# working.net
KiCad netlist of a schematic drawn in EAGLE
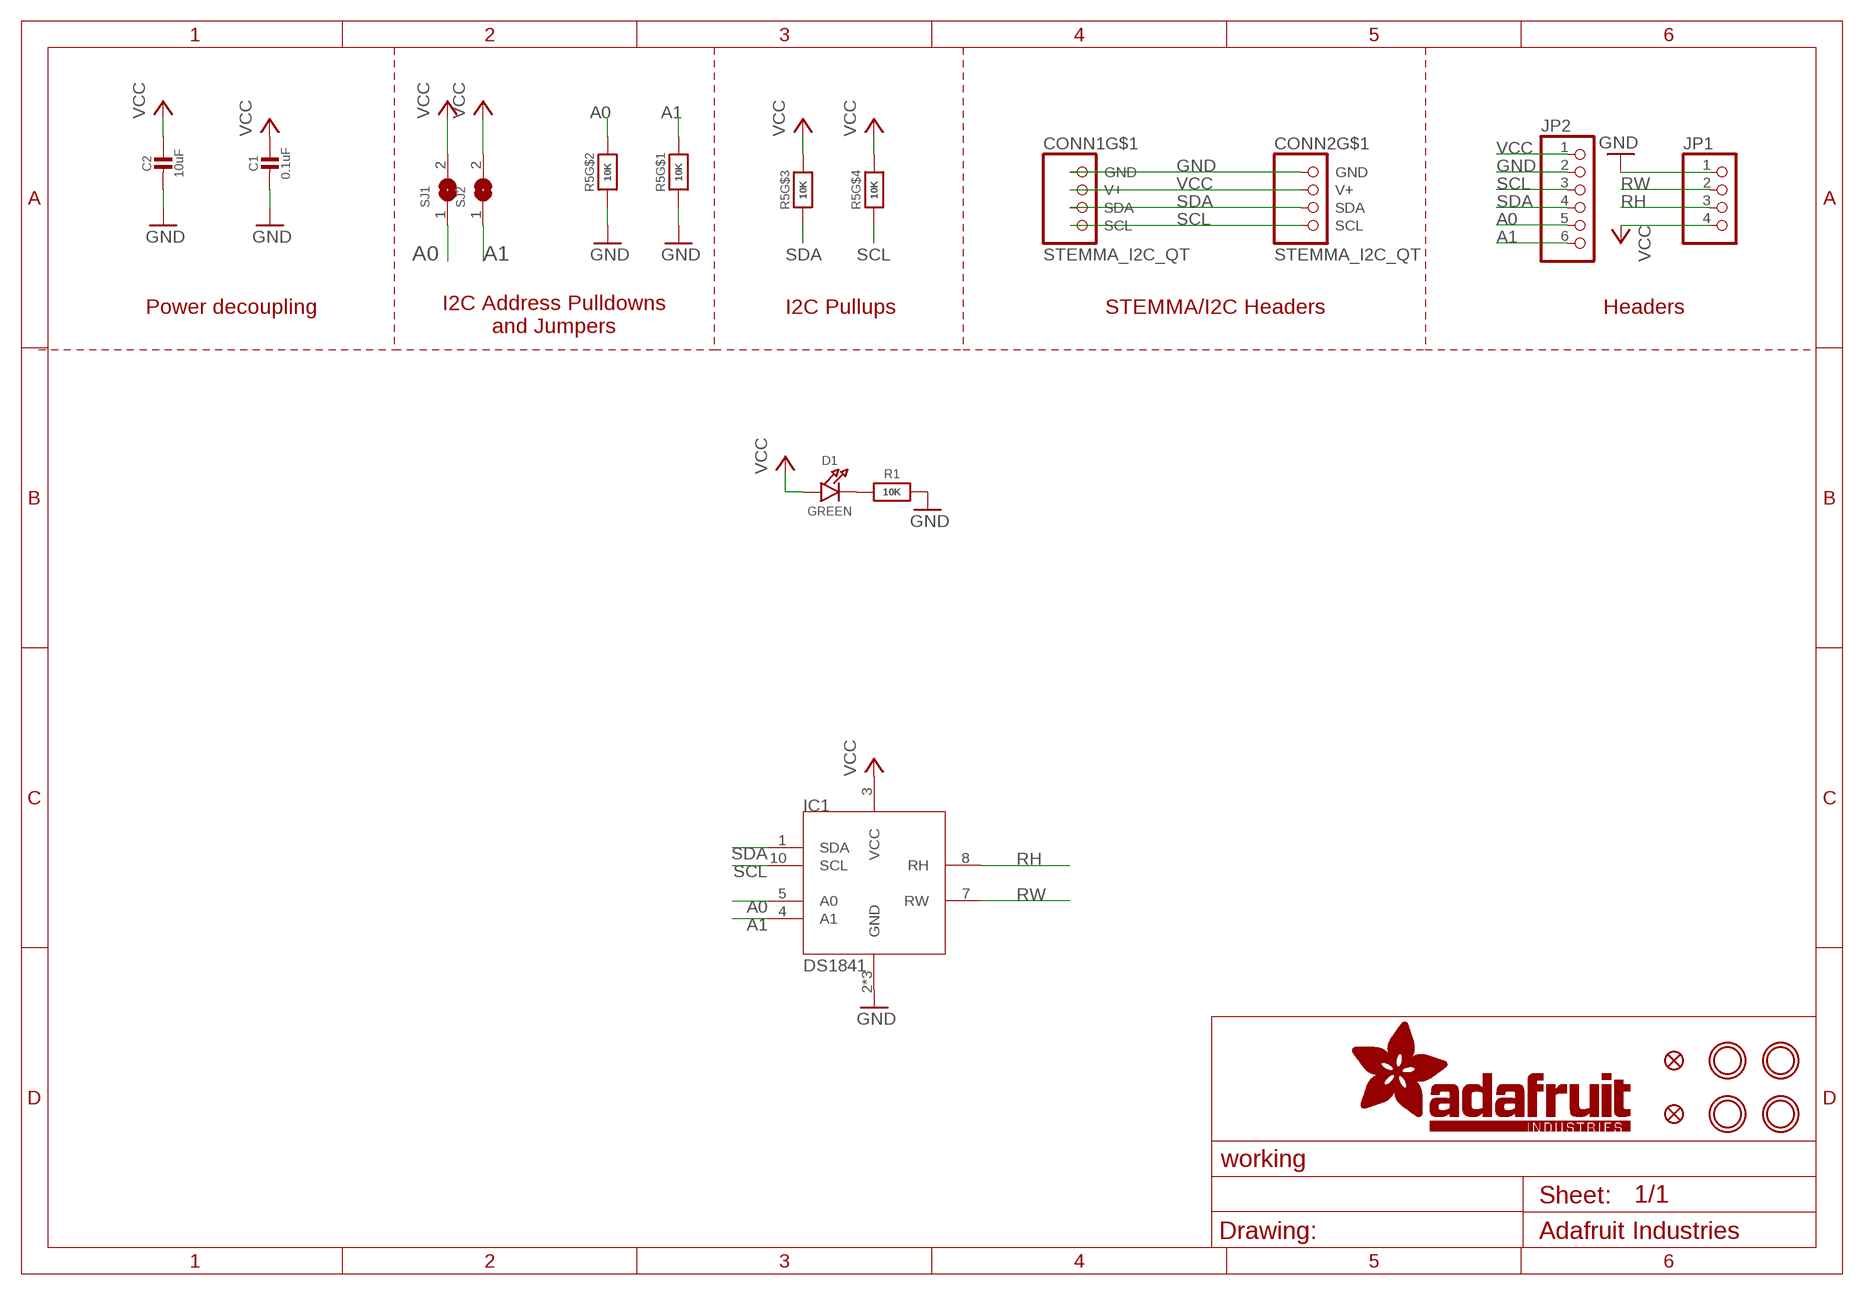
[diagram p0: schematic, sheet 1]

(export (version "E")
  (design (tool "Eeschema 10.0.6"))
  (components
    (comp (ref "C1")
      (value "0.1uF")
      (footprint "eagle-import:0603-NO")
      (libsource (lib "eagle-import") (part "CAP_CERAMIC0603_NO"))
    )
    (comp (ref "C2")
      (value "10uF")
      (footprint "eagle-import:0805-NO")
      (libsource (lib "eagle-import") (part "CAP_CERAMIC0805-NOOUTLINE"))
    )
    (comp (ref "CONN1")
      (value "STEMMA_I2C_QT")
      (footprint "eagle-import:JST_SH4")
      (libsource (lib "eagle-import") (part "STEMMA_I2C_QT"))
    )
    (comp (ref "CONN2")
      (value "STEMMA_I2C_QT")
      (footprint "eagle-import:JST_SH4")
      (libsource (lib "eagle-import") (part "STEMMA_I2C_QT"))
    )
    (comp (ref "D1")
      (value "GREEN")
      (footprint "eagle-import:CHIPLED_0603_NOOUTLINE")
      (libsource (lib "eagle-import") (part "LED0603_NOOUTLINE"))
    )
    (comp (ref "FID1")
      (value "FIDUCIAL_1MM")
      (footprint "eagle-import:FIDUCIAL_1MM")
      (libsource (lib "eagle-import") (part "FIDUCIAL_1MM"))
    )
    (comp (ref "FID2")
      (value "FIDUCIAL_1MM")
      (footprint "eagle-import:FIDUCIAL_1MM")
      (libsource (lib "eagle-import") (part "FIDUCIAL_1MM"))
    )
    (comp (ref "IC1")
      (value "DS1841")
      (footprint "eagle-import:DFN10_3X3MM")
      (libsource (lib "eagle-import") (part "DS1841"))
    )
    (comp (ref "JP1")
      (value "HEADER-1X4ROUND")
      (footprint "eagle-import:1X04_ROUND")
      (libsource (lib "eagle-import") (part "HEADER-1X4ROUND"))
    )
    (comp (ref "JP2")
      (value "HEADER-1X6ROUND")
      (footprint "eagle-import:1X06_ROUND")
      (libsource (lib "eagle-import") (part "HEADER-1X6ROUND"))
    )
    (comp (ref "R1")
      (value "10K")
      (footprint "eagle-import:0603-NO")
      (libsource (lib "eagle-import") (part "RESISTOR_0603_NOOUT"))
    )
    (comp (ref "R5")
      (value "10K")
      (footprint "eagle-import:RESPACK_4X0603")
      (libsource (lib "eagle-import") (part "RESISTOR_4PACK"))
    )
    (comp (ref "SJ1")
      (value "SOLDERJUMPER")
      (footprint "eagle-import:SOLDERJUMPER_ARROW_NOPASTE")
      (libsource (lib "eagle-import") (part "SOLDERJUMPER"))
    )
    (comp (ref "SJ2")
      (value "SOLDERJUMPER")
      (footprint "eagle-import:SOLDERJUMPER_ARROW_NOPASTE")
      (libsource (lib "eagle-import") (part "SOLDERJUMPER"))
    )
    (comp (ref "U$2")
      (value "MOUNTINGHOLE2.5")
      (footprint "eagle-import:MOUNTINGHOLE_2.5_PLATED")
      (libsource (lib "eagle-import") (part "MOUNTINGHOLE2.5"))
    )
    (comp (ref "U$3")
      (value "MOUNTINGHOLE2.5")
      (footprint "eagle-import:MOUNTINGHOLE_2.5_PLATED")
      (libsource (lib "eagle-import") (part "MOUNTINGHOLE2.5"))
    )
    (comp (ref "U$6")
      (value "MOUNTINGHOLE2.5")
      (footprint "eagle-import:MOUNTINGHOLE_2.5_PLATED")
      (libsource (lib "eagle-import") (part "MOUNTINGHOLE2.5"))
    )
    (comp (ref "U$7")
      (value "MOUNTINGHOLE2.5")
      (footprint "eagle-import:MOUNTINGHOLE_2.5_PLATED")
      (libsource (lib "eagle-import") (part "MOUNTINGHOLE2.5"))
    )
  )
  (nets
    (net (code "1") (name "/A0") (class "Default")
      (node (ref "IC1") (pin "5") (pinfunction "A0_5") (pintype "input"))
      (node (ref "JP2") (pin "5") (pinfunction "5_5") (pintype "passive"))
      (node (ref "R5") (pin "7") (pinfunction "2_7") (pintype "passive"))
      (node (ref "SJ1") (pin "1") (pinfunction "1_1") (pintype "passive"))
    )
    (net (code "2") (name "/A1") (class "Default")
      (node (ref "IC1") (pin "4") (pinfunction "A1_4") (pintype "input"))
      (node (ref "JP2") (pin "6") (pinfunction "6_6") (pintype "passive"))
      (node (ref "R5") (pin "8") (pinfunction "2_8") (pintype "passive"))
      (node (ref "SJ2") (pin "1") (pinfunction "1_1") (pintype "passive"))
    )
    (net (code "3") (name "/RH") (class "Default")
      (node (ref "IC1") (pin "8") (pinfunction "RH_8") (pintype "passive"))
      (node (ref "JP1") (pin "3") (pinfunction "3_3") (pintype "passive"))
    )
    (net (code "4") (name "/RW") (class "Default")
      (node (ref "IC1") (pin "7") (pinfunction "RW_7") (pintype "passive"))
      (node (ref "JP1") (pin "2") (pinfunction "2_2") (pintype "passive"))
    )
    (net (code "5") (name "/SCL") (class "Default")
      (node (ref "CONN1") (pin "4") (pinfunction "SCL_4") (pintype "passive"))
      (node (ref "CONN2") (pin "4") (pinfunction "SCL_4") (pintype "passive"))
      (node (ref "IC1") (pin "10") (pinfunction "SCL_10") (pintype "input"))
      (node (ref "JP2") (pin "3") (pinfunction "3_3") (pintype "passive"))
      (node (ref "R5") (pin "4") (pinfunction "1_4") (pintype "passive"))
    )
    (net (code "6") (name "/SDA") (class "Default")
      (node (ref "CONN1") (pin "3") (pinfunction "SDA_3") (pintype "passive"))
      (node (ref "CONN2") (pin "3") (pinfunction "SDA_3") (pintype "passive"))
      (node (ref "IC1") (pin "1") (pinfunction "SDA_1") (pintype "bidirectional"))
      (node (ref "JP2") (pin "4") (pinfunction "4_4") (pintype "passive"))
      (node (ref "R5") (pin "3") (pinfunction "1_3") (pintype "passive"))
    )
    (net (code "7") (name "GND") (class "Default")
      (node (ref "C1") (pin "2") (pinfunction "2_2") (pintype "passive"))
      (node (ref "C2") (pin "2") (pinfunction "2_2") (pintype "passive"))
      (node (ref "CONN1") (pin "1") (pinfunction "GND_1") (pintype "passive"))
      (node (ref "CONN2") (pin "1") (pinfunction "GND_1") (pintype "passive"))
      (node (ref "IC1") (pin "2") (pinfunction "GND_2") (pintype "power_in"))
      (node (ref "IC1") (pin "6") (pinfunction "GND_6") (pintype "power_in"))
      (node (ref "IC1") (pin "GND") (pinfunction "GND_GND") (pintype "power_in"))
      (node (ref "JP1") (pin "1") (pinfunction "1_1") (pintype "passive"))
      (node (ref "JP2") (pin "2") (pinfunction "2_2") (pintype "passive"))
      (node (ref "R1") (pin "2") (pinfunction "2_2") (pintype "passive"))
      (node (ref "R5") (pin "1") (pinfunction "1_1") (pintype "passive"))
      (node (ref "R5") (pin "2") (pinfunction "1_2") (pintype "passive"))
    )
    (net (code "8") (name "Net-(D1-PadC)") (class "Default")
      (node (ref "D1") (pin "C") (pinfunction "C_C") (pintype "passive"))
      (node (ref "R1") (pin "1") (pinfunction "1_1") (pintype "passive"))
    )
    (net (code "9") (name "VCC") (class "Default")
      (node (ref "C1") (pin "1") (pinfunction "1_1") (pintype "passive"))
      (node (ref "C2") (pin "1") (pinfunction "1_1") (pintype "passive"))
      (node (ref "CONN1") (pin "2") (pinfunction "V+_2") (pintype "passive"))
      (node (ref "CONN2") (pin "2") (pinfunction "V+_2") (pintype "passive"))
      (node (ref "D1") (pin "A") (pinfunction "A_A") (pintype "passive"))
      (node (ref "IC1") (pin "3") (pinfunction "VCC_3") (pintype "power_in"))
      (node (ref "JP1") (pin "4") (pinfunction "4_4") (pintype "passive"))
      (node (ref "JP2") (pin "1") (pinfunction "1_1") (pintype "passive"))
      (node (ref "R5") (pin "5") (pinfunction "2_5") (pintype "passive"))
      (node (ref "R5") (pin "6") (pinfunction "2_6") (pintype "passive"))
      (node (ref "SJ1") (pin "2") (pinfunction "2_2") (pintype "passive"))
      (node (ref "SJ2") (pin "2") (pinfunction "2_2") (pintype "passive"))
    )
  )
)
